# motors_motherBoard_simple_v2.net
KiCad netlist of a schematic drawn in EAGLE
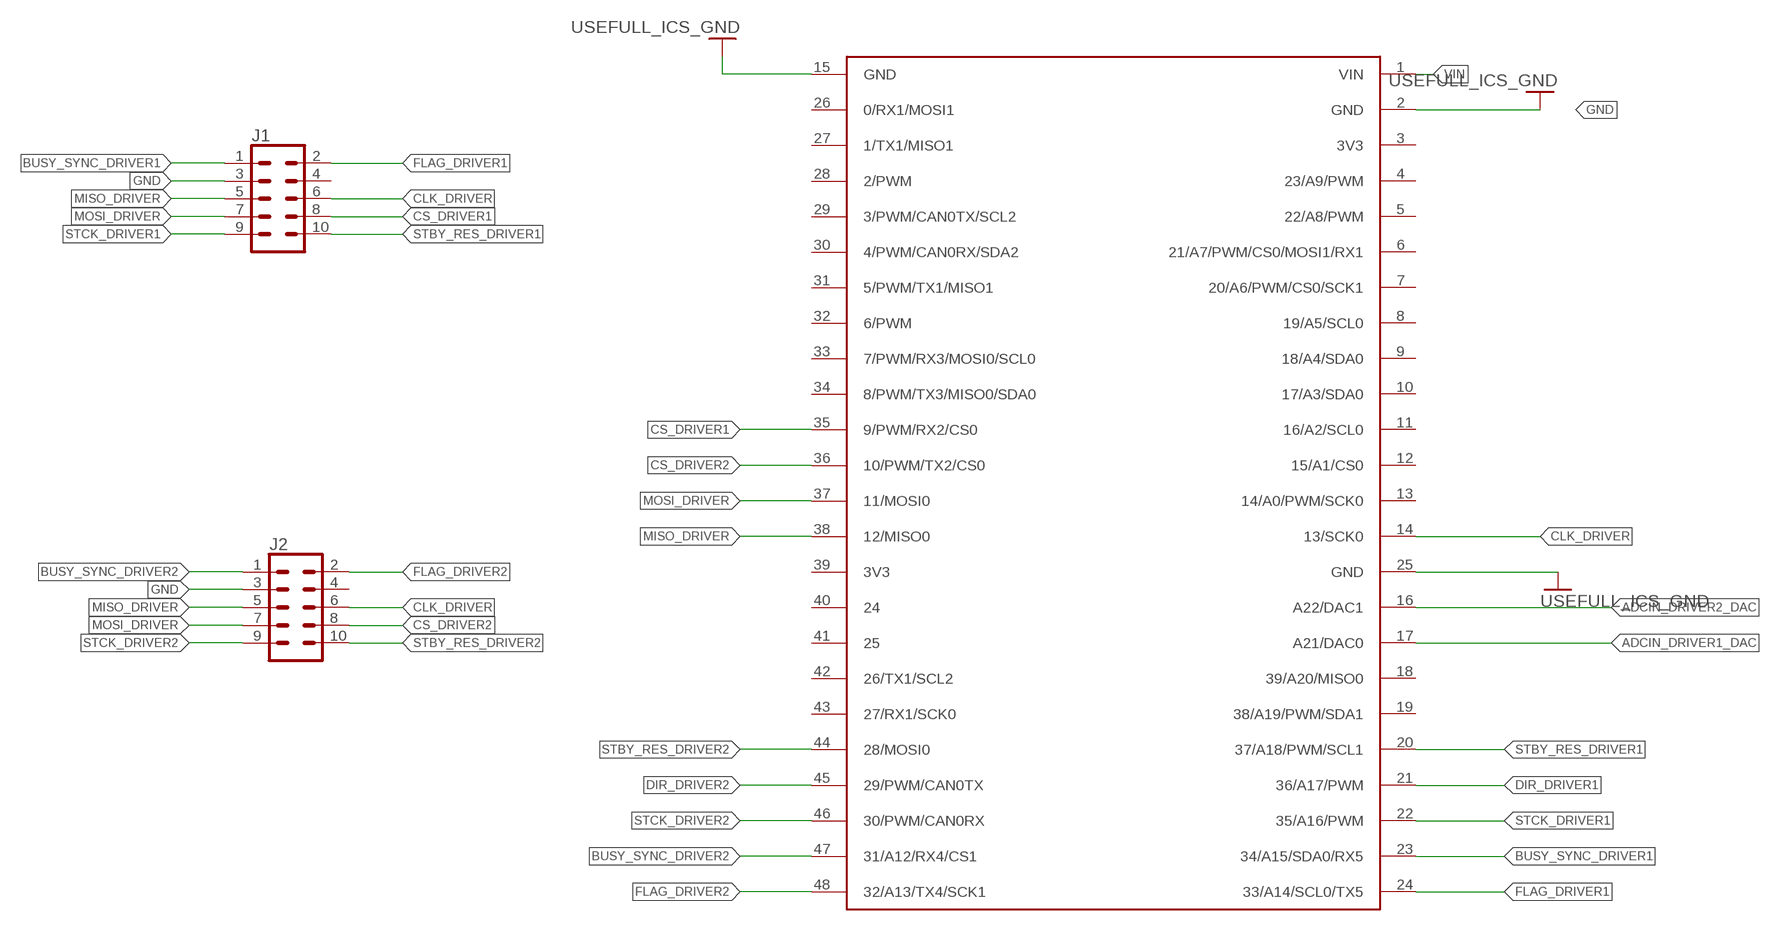
[diagram p0: schematic, sheet 1]

(export (version "E")
  (design (tool "Eeschema 10.0.6"))
  (components
    (comp (ref "J1")
      (value "SPARKFUN-CONNECTORS_CONN_05X2SHD_LOCK")
      (footprint "eagle-import:SPARKFUN-CONNECTORS_2X5-SHROUDED_LOCK")
      (libsource (lib "eagle-import") (part "SPARKFUN-CONNECTORS_CONN_05X2SHD_LOCK"))
    )
    (comp (ref "J2")
      (value "SPARKFUN-CONNECTORS_CONN_05X2SHD_LOCK")
      (footprint "eagle-import:SPARKFUN-CONNECTORS_2X5-SHROUDED_LOCK")
      (libsource (lib "eagle-import") (part "SPARKFUN-CONNECTORS_CONN_05X2SHD_LOCK"))
    )
    (comp (ref "U$3")
      (value "USEFULL_ICS_TEENSY_BASE_ADAPTER")
      (footprint "eagle-import:USEFULL_ICS_TEENSY_BASE_ADAPTER")
      (libsource (lib "eagle-import") (part "USEFULL_ICS_TEENSY_BASE_ADAPTER"))
    )
  )
  (nets
    (net (code "1") (name "ADCIN_DRIVER1_DAC") (class "Default")
      (node (ref "U$3") (pin "17") (pinfunction "A21/DAC0_17") (pintype "bidirectional"))
    )
    (net (code "2") (name "ADCIN_DRIVER2_DAC") (class "Default")
      (node (ref "U$3") (pin "16") (pinfunction "A22/DAC1_16") (pintype "bidirectional"))
    )
    (net (code "3") (name "BUSY_SYNC_DRIVER1") (class "Default")
      (node (ref "J1") (pin "1") (pinfunction "1_1") (pintype "passive"))
      (node (ref "U$3") (pin "23") (pinfunction "34/A15/SDA0/RX5_23") (pintype "bidirectional"))
    )
    (net (code "4") (name "BUSY_SYNC_DRIVER2") (class "Default")
      (node (ref "J2") (pin "1") (pinfunction "1_1") (pintype "passive"))
      (node (ref "U$3") (pin "47") (pinfunction "31/A12/RX4/CS1_47") (pintype "bidirectional"))
    )
    (net (code "5") (name "CLK_DRIVER") (class "Default")
      (node (ref "J1") (pin "6") (pinfunction "6_6") (pintype "passive"))
      (node (ref "J2") (pin "6") (pinfunction "6_6") (pintype "passive"))
      (node (ref "U$3") (pin "14") (pinfunction "13/SCK0_14") (pintype "bidirectional"))
    )
    (net (code "6") (name "CS_DRIVER1") (class "Default")
      (node (ref "J1") (pin "8") (pinfunction "8_8") (pintype "passive"))
      (node (ref "U$3") (pin "35") (pinfunction "9/PWM/RX2/CS0_35") (pintype "bidirectional"))
    )
    (net (code "7") (name "CS_DRIVER2") (class "Default")
      (node (ref "J2") (pin "8") (pinfunction "8_8") (pintype "passive"))
      (node (ref "U$3") (pin "36") (pinfunction "10/PWM/TX2/CS0_36") (pintype "bidirectional"))
    )
    (net (code "8") (name "DIR_DRIVER1") (class "Default")
      (node (ref "U$3") (pin "21") (pinfunction "36/A17/PWM_21") (pintype "bidirectional"))
    )
    (net (code "9") (name "DIR_DRIVER2") (class "Default")
      (node (ref "U$3") (pin "45") (pinfunction "29/PWM/CAN0TX_45") (pintype "bidirectional"))
    )
    (net (code "10") (name "FLAG_DRIVER1") (class "Default")
      (node (ref "J1") (pin "2") (pinfunction "2_2") (pintype "passive"))
      (node (ref "U$3") (pin "24") (pinfunction "33/A14/SCL0/TX5_24") (pintype "bidirectional"))
    )
    (net (code "11") (name "FLAG_DRIVER2") (class "Default")
      (node (ref "J2") (pin "2") (pinfunction "2_2") (pintype "passive"))
      (node (ref "U$3") (pin "48") (pinfunction "32/A13/TX4/SCK1_48") (pintype "bidirectional"))
    )
    (net (code "12") (name "GND") (class "Default")
      (node (ref "J1") (pin "3") (pinfunction "3_3") (pintype "passive"))
      (node (ref "J2") (pin "3") (pinfunction "3_3") (pintype "passive"))
      (node (ref "U$3") (pin "15") (pinfunction "GND_15") (pintype "bidirectional"))
      (node (ref "U$3") (pin "2") (pinfunction "GND_2") (pintype "bidirectional"))
      (node (ref "U$3") (pin "25") (pinfunction "GND_25") (pintype "bidirectional"))
    )
    (net (code "13") (name "MISO_DRIVER") (class "Default")
      (node (ref "J1") (pin "5") (pinfunction "5_5") (pintype "passive"))
      (node (ref "J2") (pin "5") (pinfunction "5_5") (pintype "passive"))
      (node (ref "U$3") (pin "38") (pinfunction "12/MISO0_38") (pintype "bidirectional"))
    )
    (net (code "14") (name "MOSI_DRIVER") (class "Default")
      (node (ref "J1") (pin "7") (pinfunction "7_7") (pintype "passive"))
      (node (ref "J2") (pin "7") (pinfunction "7_7") (pintype "passive"))
      (node (ref "U$3") (pin "37") (pinfunction "11/MOSI0_37") (pintype "bidirectional"))
    )
    (net (code "15") (name "STBY_RES_DRIVER1") (class "Default")
      (node (ref "J1") (pin "10") (pinfunction "10_10") (pintype "passive"))
      (node (ref "U$3") (pin "20") (pinfunction "37/A18/PWM/SCL1_20") (pintype "bidirectional"))
    )
    (net (code "16") (name "STBY_RES_DRIVER2") (class "Default")
      (node (ref "J2") (pin "10") (pinfunction "10_10") (pintype "passive"))
      (node (ref "U$3") (pin "44") (pinfunction "28/MOSI0_44") (pintype "bidirectional"))
    )
    (net (code "17") (name "STCK_DRIVER1") (class "Default")
      (node (ref "J1") (pin "9") (pinfunction "9_9") (pintype "passive"))
      (node (ref "U$3") (pin "22") (pinfunction "35/A16/PWM_22") (pintype "bidirectional"))
    )
    (net (code "18") (name "STCK_DRIVER2") (class "Default")
      (node (ref "J2") (pin "9") (pinfunction "9_9") (pintype "passive"))
      (node (ref "U$3") (pin "46") (pinfunction "30/PWM/CAN0RX_46") (pintype "bidirectional"))
    )
    (net (code "19") (name "VIN") (class "Default")
      (node (ref "U$3") (pin "1") (pinfunction "VIN_1") (pintype "bidirectional"))
    )
    (net (code "20") (name "unconnected-(J1-Pad4)") (class "Default")
      (node (ref "J1") (pin "4") (pinfunction "4_4") (pintype "passive"))
    )
    (net (code "21") (name "unconnected-(J2-Pad4)") (class "Default")
      (node (ref "J2") (pin "4") (pinfunction "4_4") (pintype "passive"))
    )
    (net (code "22") (name "unconnected-(U$3-0{slash}RX1{slash}MOSI1-Pad26)") (class "Default")
      (node (ref "U$3") (pin "26") (pinfunction "0/RX1/MOSI1_26") (pintype "bidirectional"))
    )
    (net (code "23") (name "unconnected-(U$3-1{slash}TX1{slash}MISO1-Pad27)") (class "Default")
      (node (ref "U$3") (pin "27") (pinfunction "1/TX1/MISO1_27") (pintype "bidirectional"))
    )
    (net (code "24") (name "unconnected-(U$3-2{slash}PWM-Pad28)") (class "Default")
      (node (ref "U$3") (pin "28") (pinfunction "2/PWM_28") (pintype "bidirectional"))
    )
    (net (code "25") (name "unconnected-(U$3-3V3-Pad3)") (class "Default")
      (node (ref "U$3") (pin "3") (pinfunction "3V3_3") (pintype "bidirectional"))
    )
    (net (code "26") (name "unconnected-(U$3-3V3-Pad39)") (class "Default")
      (node (ref "U$3") (pin "39") (pinfunction "3V3_39") (pintype "bidirectional"))
    )
    (net (code "27") (name "unconnected-(U$3-3{slash}PWM{slash}CAN0TX{slash}SCL2-Pad29)") (class "Default")
      (node (ref "U$3") (pin "29") (pinfunction "3/PWM/CAN0TX/SCL2_29") (pintype "bidirectional"))
    )
    (net (code "28") (name "unconnected-(U$3-4{slash}PWM{slash}CAN0RX{slash}SDA2-Pad30)") (class "Default")
      (node (ref "U$3") (pin "30") (pinfunction "4/PWM/CAN0RX/SDA2_30") (pintype "bidirectional"))
    )
    (net (code "29") (name "unconnected-(U$3-5{slash}PWM{slash}TX1{slash}MISO1-Pad31)") (class "Default")
      (node (ref "U$3") (pin "31") (pinfunction "5/PWM/TX1/MISO1_31") (pintype "bidirectional"))
    )
    (net (code "30") (name "unconnected-(U$3-6{slash}PWM-Pad32)") (class "Default")
      (node (ref "U$3") (pin "32") (pinfunction "6/PWM_32") (pintype "bidirectional"))
    )
    (net (code "31") (name "unconnected-(U$3-7{slash}PWM{slash}RX3{slash}MOSI0{slash}SCL0-Pad33)") (class "Default")
      (node (ref "U$3") (pin "33") (pinfunction "7/PWM/RX3/MOSI0/SCL0_33") (pintype "bidirectional"))
    )
    (net (code "32") (name "unconnected-(U$3-8{slash}PWM{slash}TX3{slash}MISO0{slash}SDA0-Pad34)") (class "Default")
      (node (ref "U$3") (pin "34") (pinfunction "8/PWM/TX3/MISO0/SDA0_34") (pintype "bidirectional"))
    )
    (net (code "33") (name "unconnected-(U$3-14{slash}A0{slash}PWM{slash}SCK0-Pad13)") (class "Default")
      (node (ref "U$3") (pin "13") (pinfunction "14/A0/PWM/SCK0_13") (pintype "bidirectional"))
    )
    (net (code "34") (name "unconnected-(U$3-15{slash}A1{slash}CS0-Pad12)") (class "Default")
      (node (ref "U$3") (pin "12") (pinfunction "15/A1/CS0_12") (pintype "bidirectional"))
    )
    (net (code "35") (name "unconnected-(U$3-16{slash}A2{slash}SCL0-Pad11)") (class "Default")
      (node (ref "U$3") (pin "11") (pinfunction "16/A2/SCL0_11") (pintype "bidirectional"))
    )
    (net (code "36") (name "unconnected-(U$3-17{slash}A3{slash}SDA0-Pad10)") (class "Default")
      (node (ref "U$3") (pin "10") (pinfunction "17/A3/SDA0_10") (pintype "bidirectional"))
    )
    (net (code "37") (name "unconnected-(U$3-18{slash}A4{slash}SDA0-Pad9)") (class "Default")
      (node (ref "U$3") (pin "9") (pinfunction "18/A4/SDA0_9") (pintype "bidirectional"))
    )
    (net (code "38") (name "unconnected-(U$3-19{slash}A5{slash}SCL0-Pad8)") (class "Default")
      (node (ref "U$3") (pin "8") (pinfunction "19/A5/SCL0_8") (pintype "bidirectional"))
    )
    (net (code "39") (name "unconnected-(U$3-20{slash}A6{slash}PWM{slash}CS0{slash}SCK1-Pad7)") (class "Default")
      (node (ref "U$3") (pin "7") (pinfunction "20/A6/PWM/CS0/SCK1_7") (pintype "bidirectional"))
    )
    (net (code "40") (name "unconnected-(U$3-21{slash}A7{slash}PWM{slash}CS0{slash}MOSI1{slash}RX1-Pad6)") (class "Default")
      (node (ref "U$3") (pin "6") (pinfunction "21/A7/PWM/CS0/MOSI1/RX1_6") (pintype "bidirectional"))
    )
    (net (code "41") (name "unconnected-(U$3-22{slash}A8{slash}PWM-Pad5)") (class "Default")
      (node (ref "U$3") (pin "5") (pinfunction "22/A8/PWM_5") (pintype "bidirectional"))
    )
    (net (code "42") (name "unconnected-(U$3-23{slash}A9{slash}PWM-Pad4)") (class "Default")
      (node (ref "U$3") (pin "4") (pinfunction "23/A9/PWM_4") (pintype "bidirectional"))
    )
    (net (code "43") (name "unconnected-(U$3-24-Pad40)") (class "Default")
      (node (ref "U$3") (pin "40") (pinfunction "24_40") (pintype "bidirectional"))
    )
    (net (code "44") (name "unconnected-(U$3-25-Pad41)") (class "Default")
      (node (ref "U$3") (pin "41") (pinfunction "25_41") (pintype "bidirectional"))
    )
    (net (code "45") (name "unconnected-(U$3-26{slash}TX1{slash}SCL2-Pad42)") (class "Default")
      (node (ref "U$3") (pin "42") (pinfunction "26/TX1/SCL2_42") (pintype "bidirectional"))
    )
    (net (code "46") (name "unconnected-(U$3-27{slash}RX1{slash}SCK0-Pad43)") (class "Default")
      (node (ref "U$3") (pin "43") (pinfunction "27/RX1/SCK0_43") (pintype "bidirectional"))
    )
    (net (code "47") (name "unconnected-(U$3-38{slash}A19{slash}PWM{slash}SDA1-Pad19)") (class "Default")
      (node (ref "U$3") (pin "19") (pinfunction "38/A19/PWM/SDA1_19") (pintype "bidirectional"))
    )
    (net (code "48") (name "unconnected-(U$3-39{slash}A20{slash}MISO0-Pad18)") (class "Default")
      (node (ref "U$3") (pin "18") (pinfunction "39/A20/MISO0_18") (pintype "bidirectional"))
    )
  )
)
